# Sheet1.net
KiCad netlist of a schematic drawn in Altium Designer
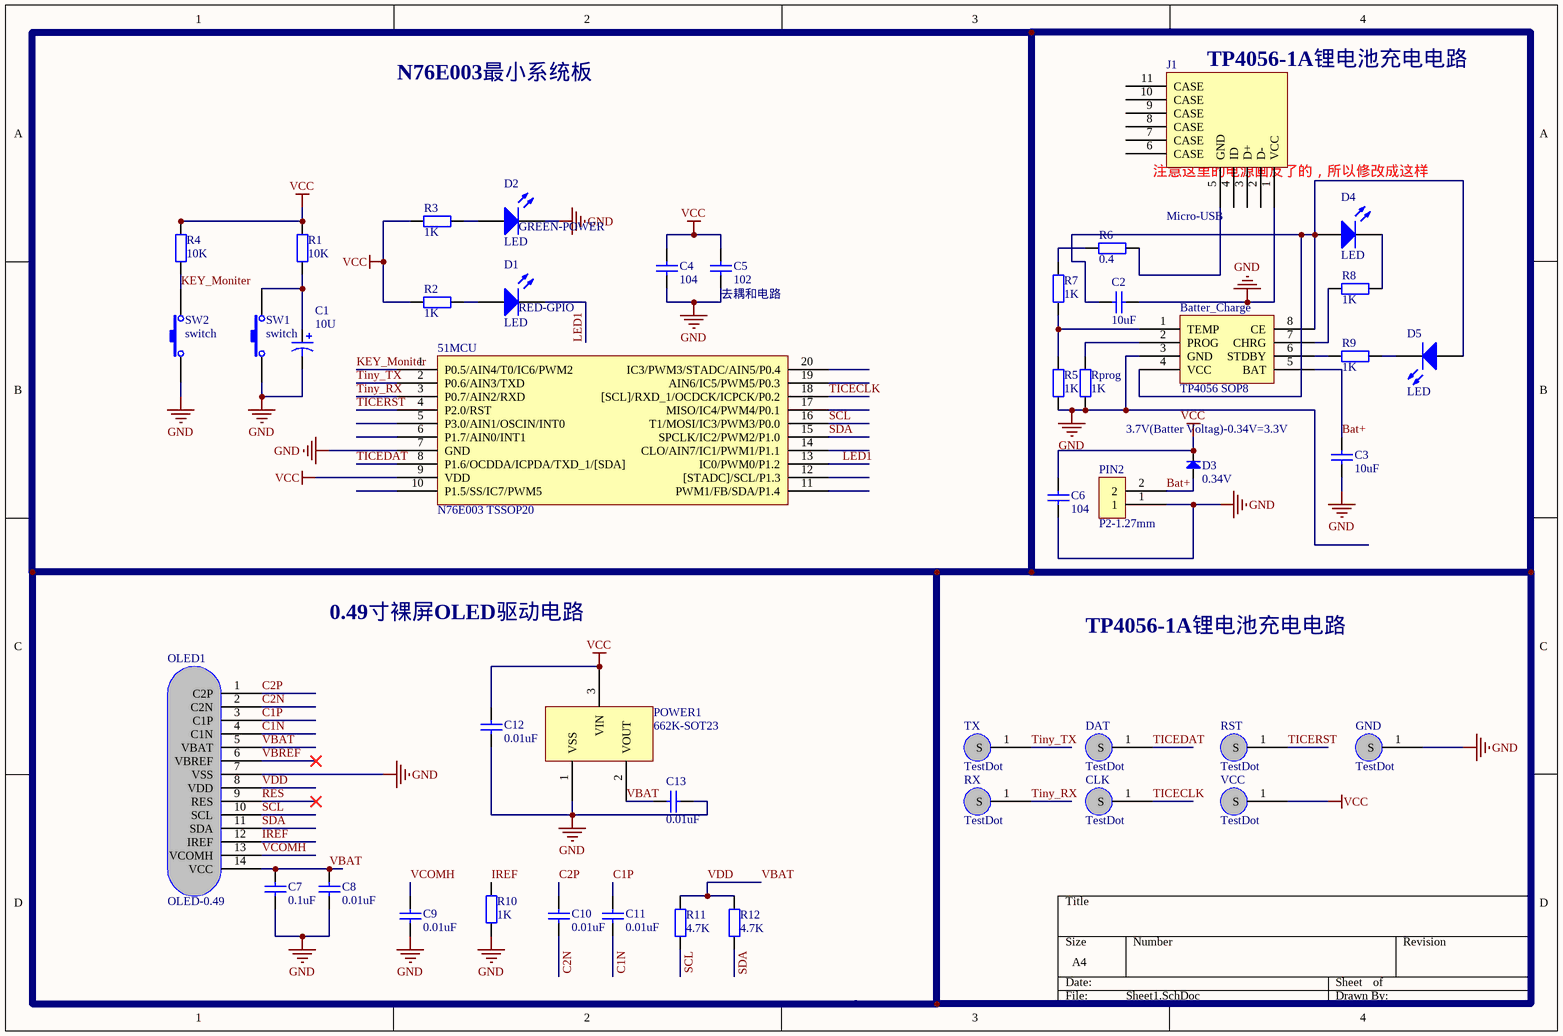
[diagram p0: Sheet1.SchDoc]

(export (version "E")
  (design (tool "Eeschema 10.0.6"))
  (components
    (comp (ref "51MCU")
      (value "N76E003 TSSOP20")
      (footprint "TSSOP20")
      (libsource (lib "Integrated_Library1") (part "N76E003 TSSOP20"))
    )
    (comp (ref "Batter_Charge")
      (value "TP4056 SOP8")
      (footprint "SOP8")
      (libsource (lib "Integrated_Library1") (part "TP4056 SOP8"))
    )
    (comp (ref "C1")
      (value "10U")
      (footprint "0805P")
      (libsource (lib "lucifer-PCBLIB_V2.0（这是老蒋的）") (part "cap(polarity)"))
    )
    (comp (ref "C2")
      (value "10uF")
      (footprint "0603C")
      (libsource (lib "lucifer-PCBLIB_V2.0（这是老蒋的）") (part "cap"))
    )
    (comp (ref "C3")
      (value "10uF")
      (footprint "0603C")
      (libsource (lib "lucifer-PCBLIB_V2.0（这是老蒋的）") (part "cap"))
    )
    (comp (ref "C4")
      (value "104")
      (footprint "0603C")
      (libsource (lib "lucifer-PCBLIB_V2.0（这是老蒋的）") (part "cap"))
    )
    (comp (ref "C5")
      (value "102")
      (footprint "0603C")
      (libsource (lib "lucifer-PCBLIB_V2.0（这是老蒋的）") (part "cap"))
    )
    (comp (ref "C6")
      (value "104")
      (footprint "0603C")
      (libsource (lib "lucifer-PCBLIB_V2.0（这是老蒋的）") (part "cap"))
    )
    (comp (ref "C7")
      (value "0.1uF")
      (footprint "CAP_0402_SMD")
      (description "Capacitor")
      (fields
        (field (name "MANUFACTURER") "Generic Components")
        (field (name "PUBLISHER") "Altium Hobart Technology Centre")
      )
      (libsource (lib "HV9006_MEASUREBOARD") (part "Cap"))
    )
    (comp (ref "C8")
      (value "0.01uF")
      (footprint "CAP_0402_SMD")
      (description "Capacitor")
      (fields
        (field (name "MANUFACTURER") "Generic Components")
        (field (name "PUBLISHER") "Altium Hobart Technology Centre")
      )
      (libsource (lib "HV9006_MEASUREBOARD") (part "Cap"))
    )
    (comp (ref "C9")
      (value "0.01uF")
      (footprint "CAP_0402_SMD")
      (description "Capacitor")
      (fields
        (field (name "MANUFACTURER") "Generic Components")
        (field (name "PUBLISHER") "Altium Hobart Technology Centre")
      )
      (libsource (lib "HV9006_MEASUREBOARD") (part "Cap"))
    )
    (comp (ref "C10")
      (value "0.01uF")
      (footprint "CAP_0402_SMD")
      (description "Capacitor")
      (fields
        (field (name "MANUFACTURER") "Generic Components")
        (field (name "PUBLISHER") "Altium Hobart Technology Centre")
      )
      (libsource (lib "HV9006_MEASUREBOARD") (part "Cap"))
    )
    (comp (ref "C11")
      (value "0.01uF")
      (footprint "CAP_0402_SMD")
      (description "Capacitor")
      (fields
        (field (name "MANUFACTURER") "Generic Components")
        (field (name "PUBLISHER") "Altium Hobart Technology Centre")
      )
      (libsource (lib "HV9006_MEASUREBOARD") (part "Cap"))
    )
    (comp (ref "C12")
      (value "0.01uF")
      (footprint "CAP_0402_SMD")
      (description "Capacitor")
      (fields
        (field (name "MANUFACTURER") "Generic Components")
        (field (name "PUBLISHER") "Altium Hobart Technology Centre")
      )
      (libsource (lib "HV9006_MEASUREBOARD") (part "Cap"))
    )
    (comp (ref "C13")
      (value "0.01uF")
      (footprint "CAP_0402_SMD")
      (description "Capacitor")
      (fields
        (field (name "MANUFACTURER") "Generic Components")
        (field (name "PUBLISHER") "Altium Hobart Technology Centre")
      )
      (libsource (lib "HV9006_MEASUREBOARD") (part "Cap"))
    )
    (comp (ref "CLK")
      (value "TestDot")
      (footprint "Single-Dot")
      (libsource (lib "Integrated_Library1") (part "TestDot"))
    )
    (comp (ref "D1")
      (value "LED")
      (footprint "0805P")
      (libsource (lib "lucifer-PCBLIB_V2.0（这是老蒋的）") (part "LED"))
    )
    (comp (ref "D2")
      (value "LED")
      (footprint "0805P")
      (libsource (lib "lucifer-PCBLIB_V2.0（这是老蒋的）") (part "LED"))
    )
    (comp (ref "D3")
      (value "0.34V")
      (footprint "1206D")
      (libsource (lib "lucifer-PCBLIB_V2.0（这是老蒋的）") (part "Diode Zener 稳压"))
    )
    (comp (ref "D4")
      (value "LED")
      (footprint "0805P")
      (libsource (lib "lucifer-PCBLIB_V2.0（这是老蒋的）") (part "LED"))
    )
    (comp (ref "D5")
      (value "LED")
      (footprint "0805P")
      (libsource (lib "lucifer-PCBLIB_V2.0（这是老蒋的）") (part "LED"))
    )
    (comp (ref "DAT")
      (value "TestDot")
      (footprint "Single-Dot")
      (libsource (lib "Integrated_Library1") (part "TestDot"))
    )
    (comp (ref "GND")
      (value "TestDot")
      (footprint "Single-Dot")
      (libsource (lib "Integrated_Library1") (part "TestDot"))
    )
    (comp (ref "J1")
      (value "Micro-USB")
      (footprint "Micro-USB")
      (libsource (lib "HV9006_MEASUREBOARD") (part "Micro-USB"))
    )
    (comp (ref "OLED1")
      (value "OLED-0.49")
      (footprint "OLED-0.49")
      (libsource (lib "Integrated_Library1") (part "OLED-0.49"))
    )
    (comp (ref "PIN2")
      (value "P2-1.27mm")
      (footprint "Pin2-1.27mm")
      (libsource (lib "Integrated_Library1") (part "P2-1.27mm"))
    )
    (comp (ref "POWER1")
      (value "662K-SOT23")
      (footprint "SOT-23")
      (libsource (lib "Integrated_Library1") (part "662K-SOT23"))
    )
    (comp (ref "R1")
      (value "10K")
      (footprint "RES_0402_SMD")
      (description "Resistor")
      (fields
        (field (name "MANUFACTURER") "Generic Components")
        (field (name "PUBLISHER") "Altium Hobart Technology Centre")
      )
      (libsource (lib "HV9006_MEASUREBOARD") (part "Res2"))
    )
    (comp (ref "R2")
      (value "1K")
      (footprint "RES_0402_SMD")
      (description "Resistor")
      (fields
        (field (name "MANUFACTURER") "Generic Components")
        (field (name "PUBLISHER") "Altium Hobart Technology Centre")
      )
      (libsource (lib "") (part "Res2_1"))
    )
    (comp (ref "R3")
      (value "1K")
      (footprint "RES_0402_SMD")
      (description "Resistor")
      (fields
        (field (name "MANUFACTURER") "Generic Components")
        (field (name "PUBLISHER") "Altium Hobart Technology Centre")
      )
      (libsource (lib "") (part "Res2_1"))
    )
    (comp (ref "R4")
      (value "10K")
      (footprint "RES_0402_SMD")
      (description "Resistor")
      (fields
        (field (name "MANUFACTURER") "Generic Components")
        (field (name "PUBLISHER") "Altium Hobart Technology Centre")
      )
      (libsource (lib "HV9006_MEASUREBOARD") (part "Res2"))
    )
    (comp (ref "R5")
      (value "1K")
      (footprint "0402")
      (description "small resistor")
      (libsource (lib "") (part "resistor_2"))
    )
    (comp (ref "R6")
      (value "0.4")
      (footprint "0402")
      (description "small resistor")
      (libsource (lib "") (part "resistor_3"))
    )
    (comp (ref "R7")
      (value "1K")
      (footprint "0402")
      (description "small resistor")
      (libsource (lib "lucifer-PCBLIB_V2.0（这是老蒋的）") (part "resistor"))
    )
    (comp (ref "R8")
      (value "1K")
      (footprint "0402")
      (description "small resistor")
      (libsource (lib "") (part "resistor_1"))
    )
    (comp (ref "R9")
      (value "1K")
      (footprint "0402")
      (description "small resistor")
      (libsource (lib "") (part "resistor_1"))
    )
    (comp (ref "R10")
      (value "1K")
      (footprint "RES_0402_SMD")
      (description "Resistor")
      (fields
        (field (name "MANUFACTURER") "Generic Components")
        (field (name "PUBLISHER") "Altium Hobart Technology Centre")
      )
      (libsource (lib "HV9006_MEASUREBOARD") (part "Res2"))
    )
    (comp (ref "R11")
      (value "4.7K")
      (footprint "RES_0402_SMD")
      (description "Resistor")
      (fields
        (field (name "MANUFACTURER") "Generic Components")
        (field (name "PUBLISHER") "Altium Hobart Technology Centre")
      )
      (libsource (lib "HV9006_MEASUREBOARD") (part "Res2"))
    )
    (comp (ref "R12")
      (value "4.7K")
      (footprint "RES_0402_SMD")
      (description "Resistor")
      (fields
        (field (name "MANUFACTURER") "Generic Components")
        (field (name "PUBLISHER") "Altium Hobart Technology Centre")
      )
      (libsource (lib "HV9006_MEASUREBOARD") (part "Res2"))
    )
    (comp (ref "Rprog")
      (value "1K")
      (footprint "0402")
      (description "small resistor")
      (libsource (lib "") (part "resistor_2"))
    )
    (comp (ref "RST")
      (value "TestDot")
      (footprint "Single-Dot")
      (libsource (lib "Integrated_Library1") (part "TestDot"))
    )
    (comp (ref "RX")
      (value "TestDot")
      (footprint "Single-Dot")
      (libsource (lib "Integrated_Library1") (part "TestDot"))
    )
    (comp (ref "SW1")
      (value "switch")
      (footprint "SWITCH-微型")
      (libsource (lib "lucifer-PCBLIB_V2.0（这是老蒋的）") (part "switch-1"))
    )
    (comp (ref "SW2")
      (value "switch")
      (footprint "SWITCH-微型")
      (libsource (lib "lucifer-PCBLIB_V2.0（这是老蒋的）") (part "switch-1"))
    )
    (comp (ref "TX")
      (value "TestDot")
      (footprint "Single-Dot")
      (libsource (lib "Integrated_Library1") (part "TestDot"))
    )
    (comp (ref "VCC")
      (value "TestDot")
      (footprint "Single-Dot")
      (libsource (lib "Integrated_Library1") (part "TestDot"))
    )
  )
  (nets
    (net (code "1") (name "/Bat+") (class "Default")
      (node (ref "Batter_Charge") (pin "5") (pinfunction "BAT_5") (pintype "passive"))
      (node (ref "C3") (pin "2") (pinfunction "2_2") (pintype "passive"))
      (node (ref "D3") (pin "1") (pinfunction "A_1") (pintype "passive"))
      (node (ref "PIN2") (pin "2") (pinfunction "2_2") (pintype "passive"))
    )
    (net (code "2") (name "/C1N") (class "Default")
      (node (ref "C11") (pin "2") (pinfunction "2_2") (pintype "passive"))
      (node (ref "OLED1") (pin "4") (pinfunction "C1N_4") (pintype "passive"))
    )
    (net (code "3") (name "/C1P") (class "Default")
      (node (ref "C11") (pin "1") (pinfunction "1_1") (pintype "passive"))
      (node (ref "OLED1") (pin "3") (pinfunction "C1P_3") (pintype "passive"))
    )
    (net (code "4") (name "/C2N") (class "Default")
      (node (ref "C10") (pin "2") (pinfunction "2_2") (pintype "passive"))
      (node (ref "OLED1") (pin "2") (pinfunction "C2N_2") (pintype "passive"))
    )
    (net (code "5") (name "/C2P") (class "Default")
      (node (ref "C10") (pin "1") (pinfunction "1_1") (pintype "passive"))
      (node (ref "OLED1") (pin "1") (pinfunction "C2P_1") (pintype "passive"))
    )
    (net (code "6") (name "/IREF") (class "Default")
      (node (ref "OLED1") (pin "12") (pinfunction "IREF_12") (pintype "passive"))
      (node (ref "R10") (pin "2") (pinfunction "2_2") (pintype "passive"))
    )
    (net (code "7") (name "/KEY_Moniter") (class "Default")
      (node (ref "51MCU") (pin "1") (pinfunction "P0.5/AIN4/T0/IC6/PWM2_1") (pintype "passive"))
      (node (ref "R4") (pin "1") (pinfunction "1_1") (pintype "passive"))
      (node (ref "SW2") (pin "2") (pinfunction "2_2") (pintype "passive"))
    )
    (net (code "8") (name "/LED1") (class "Default")
      (node (ref "51MCU") (pin "13") (pinfunction "IC0/PWM0/P1.2_13") (pintype "passive"))
      (node (ref "D1") (pin "2") (pinfunction "K_2") (pintype "passive"))
    )
    (net (code "9") (name "/RES") (class "Default")
      (node (ref "OLED1") (pin "9") (pinfunction "RES_9") (pintype "passive+no_connect"))
    )
    (net (code "10") (name "/SCL") (class "Default")
      (node (ref "51MCU") (pin "16") (pinfunction "T1/MOSI/IC3/PWM3/P0.0_16") (pintype "passive"))
      (node (ref "OLED1") (pin "10") (pinfunction "SCL_10") (pintype "passive"))
      (node (ref "R11") (pin "1") (pinfunction "1_1") (pintype "passive"))
    )
    (net (code "11") (name "/SDA") (class "Default")
      (node (ref "51MCU") (pin "15") (pinfunction "SPCLK/IC2/PWM2/P1.0_15") (pintype "passive"))
      (node (ref "OLED1") (pin "11") (pinfunction "SDA_11") (pintype "passive"))
      (node (ref "R12") (pin "1") (pinfunction "1_1") (pintype "passive"))
    )
    (net (code "12") (name "/TICECLK") (class "Default")
      (node (ref "51MCU") (pin "18") (pinfunction "[SCL]/RXD_1/OCDCK/ICPCK/P0.2_18") (pintype "passive"))
      (node (ref "CLK") (pin "1") (pinfunction "S_1") (pintype "passive"))
    )
    (net (code "13") (name "/TICEDAT") (class "Default")
      (node (ref "51MCU") (pin "8") (pinfunction "P1.6/OCDDA/ICPDA/TXD_1/[SDA]_8") (pintype "passive"))
      (node (ref "DAT") (pin "1") (pinfunction "S_1") (pintype "passive"))
    )
    (net (code "14") (name "/TICERST") (class "Default")
      (node (ref "51MCU") (pin "4") (pinfunction "P2.0/RST_4") (pintype "passive"))
      (node (ref "RST") (pin "1") (pinfunction "S_1") (pintype "passive"))
    )
    (net (code "15") (name "/Tiny_RX") (class "Default")
      (node (ref "51MCU") (pin "3") (pinfunction "P0.7/AIN2/RXD_3") (pintype "passive"))
      (node (ref "RX") (pin "1") (pinfunction "S_1") (pintype "passive"))
    )
    (net (code "16") (name "/Tiny_TX") (class "Default")
      (node (ref "51MCU") (pin "2") (pinfunction "P0.6/AIN3/TXD_2") (pintype "passive"))
      (node (ref "TX") (pin "1") (pinfunction "S_1") (pintype "passive"))
    )
    (net (code "17") (name "/VBAT") (class "Default")
      (node (ref "C13") (pin "1") (pinfunction "1_1") (pintype "passive"))
      (node (ref "C7") (pin "2") (pinfunction "2_2") (pintype "passive"))
      (node (ref "C8") (pin "1") (pinfunction "1_1") (pintype "passive"))
      (node (ref "OLED1") (pin "14") (pinfunction "VCC_14") (pintype "passive"))
      (node (ref "OLED1") (pin "5") (pinfunction "VBAT_5") (pintype "passive"))
      (node (ref "OLED1") (pin "8") (pinfunction "VDD_8") (pintype "passive"))
      (node (ref "POWER1") (pin "2") (pinfunction "VOUT_2") (pintype "passive"))
      (node (ref "R11") (pin "2") (pinfunction "2_2") (pintype "passive"))
      (node (ref "R12") (pin "2") (pinfunction "2_2") (pintype "passive"))
    )
    (net (code "18") (name "/VBREF") (class "Default")
      (node (ref "OLED1") (pin "6") (pinfunction "VBREF_6") (pintype "passive+no_connect"))
    )
    (net (code "19") (name "/VCOMH") (class "Default")
      (node (ref "C9") (pin "1") (pinfunction "1_1") (pintype "passive"))
      (node (ref "OLED1") (pin "13") (pinfunction "VCOMH_13") (pintype "passive"))
    )
    (net (code "20") (name "GND") (class "Default")
      (node (ref "51MCU") (pin "7") (pinfunction "GND_7") (pintype "passive"))
      (node (ref "Batter_Charge") (pin "3") (pinfunction "GND_3") (pintype "passive"))
      (node (ref "C1") (pin "2") (pinfunction "2_2") (pintype "passive"))
      (node (ref "C12") (pin "2") (pinfunction "2_2") (pintype "passive"))
      (node (ref "C13") (pin "2") (pinfunction "2_2") (pintype "passive"))
      (node (ref "C2") (pin "2") (pinfunction "2_2") (pintype "passive"))
      (node (ref "C3") (pin "1") (pinfunction "1_1") (pintype "passive"))
      (node (ref "C4") (pin "1") (pinfunction "1_1") (pintype "passive"))
      (node (ref "C5") (pin "1") (pinfunction "1_1") (pintype "passive"))
      (node (ref "C6") (pin "1") (pinfunction "1_1") (pintype "passive"))
      (node (ref "C7") (pin "1") (pinfunction "1_1") (pintype "passive"))
      (node (ref "C8") (pin "2") (pinfunction "2_2") (pintype "passive"))
      (node (ref "C9") (pin "2") (pinfunction "2_2") (pintype "passive"))
      (node (ref "D2") (pin "2") (pinfunction "K_2") (pintype "passive"))
      (node (ref "GND") (pin "1") (pinfunction "S_1") (pintype "passive"))
      (node (ref "J1") (pin "1") (pinfunction "VCC_1") (pintype "passive"))
      (node (ref "OLED1") (pin "7") (pinfunction "VSS_7") (pintype "passive"))
      (node (ref "PIN2") (pin "1") (pinfunction "1_1") (pintype "passive"))
      (node (ref "POWER1") (pin "1") (pinfunction "VSS_1") (pintype "passive"))
      (node (ref "R10") (pin "1") (pinfunction "1_1") (pintype "passive"))
      (node (ref "R5") (pin "1") (pinfunction "1_1") (pintype "passive"))
      (node (ref "Rprog") (pin "1") (pinfunction "1_1") (pintype "passive"))
      (node (ref "SW1") (pin "1") (pinfunction "1_1") (pintype "passive"))
      (node (ref "SW2") (pin "1") (pinfunction "1_1") (pintype "passive"))
    )
    (net (code "21") (name "Net-(Batter_Charge-CE)") (class "Default")
      (node (ref "Batter_Charge") (pin "4") (pinfunction "VCC_4") (pintype "passive"))
      (node (ref "Batter_Charge") (pin "8") (pinfunction "CE_8") (pintype "passive"))
      (node (ref "C2") (pin "1") (pinfunction "1_1") (pintype "passive"))
      (node (ref "D4") (pin "1") (pinfunction "A_1") (pintype "passive"))
      (node (ref "D5") (pin "1") (pinfunction "A_1") (pintype "passive"))
    )
    (net (code "22") (name "Net-(Batter_Charge-CHRG)") (class "Default")
      (node (ref "Batter_Charge") (pin "7") (pinfunction "CHRG_7") (pintype "passive"))
      (node (ref "R8") (pin "1") (pinfunction "1_1") (pintype "passive"))
    )
    (net (code "23") (name "Net-(Batter_Charge-PROG)") (class "Default")
      (node (ref "Batter_Charge") (pin "2") (pinfunction "PROG_2") (pintype "passive"))
      (node (ref "Rprog") (pin "2") (pinfunction "2_2") (pintype "passive"))
    )
    (net (code "24") (name "Net-(Batter_Charge-STDBY)") (class "Default")
      (node (ref "Batter_Charge") (pin "6") (pinfunction "STDBY_6") (pintype "passive"))
      (node (ref "R9") (pin "1") (pinfunction "1_1") (pintype "passive"))
    )
    (net (code "25") (name "Net-(Batter_Charge-TEMP)") (class "Default")
      (node (ref "Batter_Charge") (pin "1") (pinfunction "TEMP_1") (pintype "passive"))
      (node (ref "R5") (pin "2") (pinfunction "2_2") (pintype "passive"))
      (node (ref "R7") (pin "2") (pinfunction "2_2") (pintype "passive"))
    )
    (net (code "26") (name "Net-(C1-Pad1)") (class "Default")
      (node (ref "C1") (pin "1") (pinfunction "1_1") (pintype "passive"))
      (node (ref "R1") (pin "1") (pinfunction "1_1") (pintype "passive"))
      (node (ref "SW1") (pin "2") (pinfunction "2_2") (pintype "passive"))
    )
    (net (code "27") (name "Net-(D1-A)") (class "Default")
      (node (ref "D1") (pin "1") (pinfunction "A_1") (pintype "passive"))
      (node (ref "R2") (pin "1") (pinfunction "1_1") (pintype "passive"))
    )
    (net (code "28") (name "Net-(D2-A)") (class "Default")
      (node (ref "D2") (pin "1") (pinfunction "A_1") (pintype "passive"))
      (node (ref "R3") (pin "1") (pinfunction "1_1") (pintype "passive"))
    )
    (net (code "29") (name "Net-(D4-K)") (class "Default")
      (node (ref "D4") (pin "2") (pinfunction "K_2") (pintype "passive"))
      (node (ref "R8") (pin "2") (pinfunction "2_2") (pintype "passive"))
    )
    (net (code "30") (name "Net-(D5-K)") (class "Default")
      (node (ref "D5") (pin "2") (pinfunction "K_2") (pintype "passive"))
      (node (ref "R9") (pin "2") (pinfunction "2_2") (pintype "passive"))
    )
    (net (code "31") (name "Net-(J1-GND)") (class "Default")
      (node (ref "J1") (pin "5") (pinfunction "GND_5") (pintype "passive"))
      (node (ref "R6") (pin "1") (pinfunction "1_1") (pintype "passive"))
    )
    (net (code "32") (name "Net-(R6-Pad2)") (class "Default")
      (node (ref "R6") (pin "2") (pinfunction "2_2") (pintype "passive"))
      (node (ref "R7") (pin "1") (pinfunction "1_1") (pintype "passive"))
    )
    (net (code "33") (name "VCC") (class "Default")
      (node (ref "51MCU") (pin "9") (pinfunction "VDD_9") (pintype "passive"))
      (node (ref "C12") (pin "1") (pinfunction "1_1") (pintype "passive"))
      (node (ref "C4") (pin "2") (pinfunction "2_2") (pintype "passive"))
      (node (ref "C5") (pin "2") (pinfunction "2_2") (pintype "passive"))
      (node (ref "C6") (pin "2") (pinfunction "2_2") (pintype "passive"))
      (node (ref "D3") (pin "2") (pinfunction "K_2") (pintype "passive"))
      (node (ref "POWER1") (pin "3") (pinfunction "VIN_3") (pintype "passive"))
      (node (ref "R1") (pin "2") (pinfunction "2_2") (pintype "passive"))
      (node (ref "R2") (pin "2") (pinfunction "2_2") (pintype "passive"))
      (node (ref "R3") (pin "2") (pinfunction "2_2") (pintype "passive"))
      (node (ref "R4") (pin "2") (pinfunction "2_2") (pintype "passive"))
      (node (ref "VCC") (pin "1") (pinfunction "S_1") (pintype "passive"))
    )
    (net (code "34") (name "unconnected-(51MCU-AIN6{slash}IC5{slash}PWM5{slash}P0.3-Pad19)") (class "Default")
      (node (ref "51MCU") (pin "19") (pinfunction "AIN6/IC5/PWM5/P0.3_19") (pintype "passive"))
    )
    (net (code "35") (name "unconnected-(51MCU-CLO{slash}AIN7{slash}IC1{slash}PWM1{slash}P1.1-Pad14)") (class "Default")
      (node (ref "51MCU") (pin "14") (pinfunction "CLO/AIN7/IC1/PWM1/P1.1_14") (pintype "passive"))
    )
    (net (code "36") (name "unconnected-(51MCU-IC3{slash}PWM3{slash}STADC{slash}AIN5{slash}P0.4-Pad20)") (class "Default")
      (node (ref "51MCU") (pin "20") (pinfunction "IC3/PWM3/STADC/AIN5/P0.4_20") (pintype "passive"))
    )
    (net (code "37") (name "unconnected-(51MCU-MISO{slash}IC4{slash}PWM4{slash}P0.1-Pad17)") (class "Default")
      (node (ref "51MCU") (pin "17") (pinfunction "MISO/IC4/PWM4/P0.1_17") (pintype "passive"))
    )
    (net (code "38") (name "unconnected-(51MCU-P1.5{slash}SS{slash}IC7{slash}PWM5-Pad10)") (class "Default")
      (node (ref "51MCU") (pin "10") (pinfunction "P1.5/SS/IC7/PWM5_10") (pintype "passive"))
    )
    (net (code "39") (name "unconnected-(51MCU-P1.7{slash}AIN0{slash}INT1-Pad6)") (class "Default")
      (node (ref "51MCU") (pin "6") (pinfunction "P1.7/AIN0/INT1_6") (pintype "passive"))
    )
    (net (code "40") (name "unconnected-(51MCU-P3.0{slash}AIN1{slash}OSCIN{slash}INT0-Pad5)") (class "Default")
      (node (ref "51MCU") (pin "5") (pinfunction "P3.0/AIN1/OSCIN/INT0_5") (pintype "passive"))
    )
    (net (code "41") (name "unconnected-(51MCU-PWM1{slash}FB{slash}SDA{slash}P1.4-Pad11)") (class "Default")
      (node (ref "51MCU") (pin "11") (pinfunction "PWM1/FB/SDA/P1.4_11") (pintype "passive"))
    )
    (net (code "42") (name "unconnected-(51MCU-[STADC]{slash}SCL{slash}P1.3-Pad12)") (class "Default")
      (node (ref "51MCU") (pin "12") (pinfunction "[STADC]/SCL/P1.3_12") (pintype "passive"))
    )
    (net (code "43") (name "unconnected-(J1-CASE-Pad6)") (class "Default")
      (node (ref "J1") (pin "6") (pinfunction "CASE_6") (pintype "passive"))
    )
    (net (code "44") (name "unconnected-(J1-CASE-Pad7)") (class "Default")
      (node (ref "J1") (pin "7") (pinfunction "CASE_7") (pintype "passive"))
    )
    (net (code "45") (name "unconnected-(J1-CASE-Pad8)") (class "Default")
      (node (ref "J1") (pin "8") (pinfunction "CASE_8") (pintype "passive"))
    )
    (net (code "46") (name "unconnected-(J1-CASE-Pad9)") (class "Default")
      (node (ref "J1") (pin "9") (pinfunction "CASE_9") (pintype "passive"))
    )
    (net (code "47") (name "unconnected-(J1-CASE-Pad10)") (class "Default")
      (node (ref "J1") (pin "10") (pinfunction "CASE_10") (pintype "passive"))
    )
    (net (code "48") (name "unconnected-(J1-CASE-Pad11)") (class "Default")
      (node (ref "J1") (pin "11") (pinfunction "CASE_11") (pintype "passive"))
    )
    (net (code "49") (name "unconnected-(J1-D+-Pad3)") (class "Default")
      (node (ref "J1") (pin "3") (pinfunction "D+_3") (pintype "passive"))
    )
    (net (code "50") (name "unconnected-(J1-D--Pad2)") (class "Default")
      (node (ref "J1") (pin "2") (pinfunction "D-_2") (pintype "passive"))
    )
    (net (code "51") (name "unconnected-(J1-ID-Pad4)") (class "Default")
      (node (ref "J1") (pin "4") (pinfunction "ID_4") (pintype "passive"))
    )
  )
)
